# Qwiic_Spectral_Sensor-AS726x.net
KiCad netlist of a schematic drawn in EAGLE
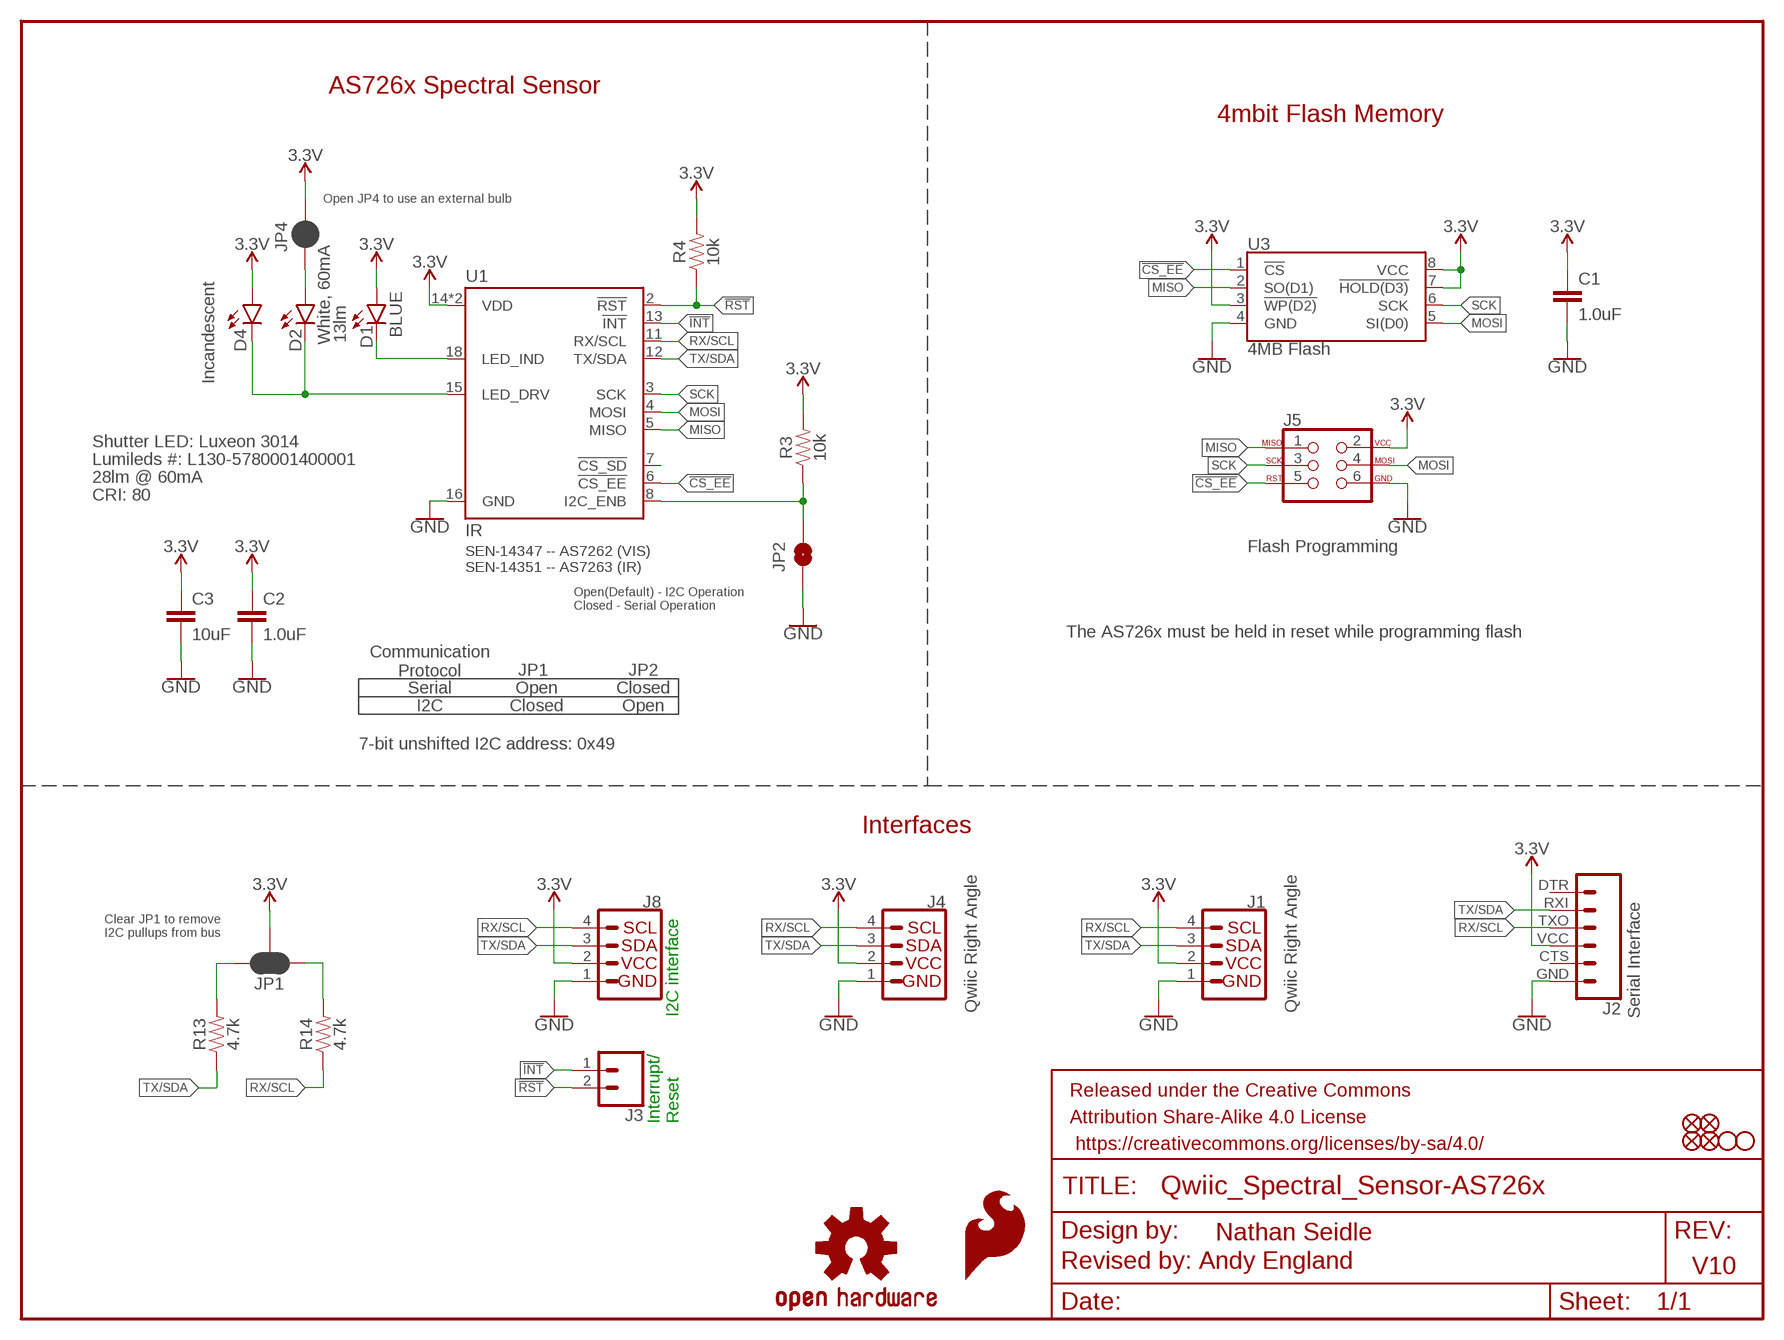
[diagram p0: schematic, sheet 1]

(export (version "E")
  (design (tool "Eeschema 10.0.6"))
  (components
    (comp (ref "C1")
      (value "1.0uF")
      (footprint "eagle-import:0603")
      (libsource (lib "eagle-import") (part "1.0UF-0603-16V-10%"))
    )
    (comp (ref "C2")
      (value "1.0uF")
      (footprint "eagle-import:0603")
      (libsource (lib "eagle-import") (part "1.0UF-0603-16V-10%"))
    )
    (comp (ref "C3")
      (value "10uF")
      (footprint "eagle-import:0603")
      (libsource (lib "eagle-import") (part "10UF-0603-6.3V-20%"))
    )
    (comp (ref "D1")
      (value "BLUE")
      (footprint "eagle-import:LED-0603")
      (libsource (lib "eagle-import") (part "LED-BLUE0603"))
    )
    (comp (ref "D2")
      (value "White, 60mA")
      (footprint "eagle-import:SUPER_BRIGHT_SMD_LED_3014")
      (libsource (lib "eagle-import") (part "LED-WHITE3014"))
    )
    (comp (ref "D4")
      (value "Incandescent")
      (footprint "eagle-import:LED_5MM_NOSILK")
      (libsource (lib "eagle-import") (part "LEDNS"))
    )
    (comp (ref "FD1")
      (value "FIDUCIAL1X2")
      (footprint "eagle-import:FIDUCIAL-1X2")
      (libsource (lib "eagle-import") (part "FIDUCIAL1X2"))
    )
    (comp (ref "FD2")
      (value "FIDUCIAL1X2")
      (footprint "eagle-import:FIDUCIAL-1X2")
      (libsource (lib "eagle-import") (part "FIDUCIAL1X2"))
    )
    (comp (ref "FD3")
      (value "FIDUCIAL1X2")
      (footprint "eagle-import:FIDUCIAL-1X2")
      (libsource (lib "eagle-import") (part "FIDUCIAL1X2"))
    )
    (comp (ref "FD4")
      (value "FIDUCIAL1X2")
      (footprint "eagle-import:FIDUCIAL-1X2")
      (libsource (lib "eagle-import") (part "FIDUCIAL1X2"))
    )
    (comp (ref "FRAME1")
      (value "FRAME-LETTER")
      (footprint "eagle-import:CREATIVE_COMMONS")
      (libsource (lib "eagle-import") (part "FRAME-LETTER"))
    )
    (comp (ref "H2")
      (value "STAND-OFF")
      (footprint "eagle-import:STAND-OFF")
      (libsource (lib "eagle-import") (part "STAND-OFF"))
    )
    (comp (ref "H4")
      (value "STAND-OFF")
      (footprint "eagle-import:STAND-OFF")
      (libsource (lib "eagle-import") (part "STAND-OFF"))
    )
    (comp (ref "J1")
      (value "Qwiic Right Angle")
      (footprint "eagle-import:1X04_1MM_RA")
      (libsource (lib "eagle-import") (part "I2C_STANDARDQWIIC"))
    )
    (comp (ref "J2")
      (value "Serial Interface")
      (footprint "eagle-import:FTDI_BASIC")
      (libsource (lib "eagle-import") (part "6_PIN_SERIAL_CABLEPTH"))
    )
    (comp (ref "J3")
      (value "CONN_021X02_NO_SILK")
      (footprint "eagle-import:1X02_NO_SILK")
      (libsource (lib "eagle-import") (part "CONN_021X02_NO_SILK"))
    )
    (comp (ref "J4")
      (value "Qwiic Right Angle")
      (footprint "eagle-import:1X04_1MM_RA")
      (libsource (lib "eagle-import") (part "I2C_STANDARDQWIIC"))
    )
    (comp (ref "J5")
      (value "Flash Programming")
      (footprint "eagle-import:2X3_TEST_POINTS")
      (libsource (lib "eagle-import") (part "AVR_SPI_PROG_3X2TESTPOINTS"))
    )
    (comp (ref "J8")
      (value "I2C_STANDARD_NO_SILK")
      (footprint "eagle-import:1X04_NO_SILK")
      (libsource (lib "eagle-import") (part "I2C_STANDARD_NO_SILK"))
    )
    (comp (ref "JP1")
      (value "JUMPER-SMT_3_2-NC_PASTE_SILK")
      (footprint "eagle-import:SMT-JUMPER_3_2-NC_PASTE_SILK")
      (libsource (lib "eagle-import") (part "JUMPER-SMT_3_2-NC_PASTE_SILK"))
    )
    (comp (ref "JP2")
      (value "JUMPER-SMT_2_NO_SILK")
      (footprint "eagle-import:SMT-JUMPER_2_NO_SILK")
      (libsource (lib "eagle-import") (part "JUMPER-SMT_2_NO_SILK"))
    )
    (comp (ref "JP4")
      (value "JUMPER-SMT_2_NC_PASTE_NO-SILK")
      (footprint "eagle-import:SMT-JUMPER_2_NC_PASTE_NO-SILK")
      (libsource (lib "eagle-import") (part "JUMPER-SMT_2_NC_PASTE_NO-SILK"))
    )
    (comp (ref "LOGO1")
      (value "SFE_LOGO_FLAME.2_INCH")
      (footprint "eagle-import:SFE_LOGO_FLAME_.2")
      (libsource (lib "eagle-import") (part "SFE_LOGO_FLAME.2_INCH"))
    )
    (comp (ref "LOGO2")
      (value "SFE_LOGO_FLAME.2_INCH")
      (footprint "eagle-import:SFE_LOGO_FLAME_.2")
      (libsource (lib "eagle-import") (part "SFE_LOGO_FLAME.2_INCH"))
    )
    (comp (ref "LOGO4")
      (value "OSHW-LOGOS")
      (footprint "eagle-import:OSHW-LOGO-S")
      (libsource (lib "eagle-import") (part "OSHW-LOGOS"))
    )
    (comp (ref "R3")
      (value "10k")
      (footprint "eagle-import:0603")
      (libsource (lib "eagle-import") (part "10KOHM-0603-1/10W-1%"))
    )
    (comp (ref "R4")
      (value "10k")
      (footprint "eagle-import:0603")
      (libsource (lib "eagle-import") (part "10KOHM-0603-1/10W-1%"))
    )
    (comp (ref "R13")
      (value "4.7k")
      (footprint "eagle-import:0603")
      (libsource (lib "eagle-import") (part "4.7KOHM-0603-1/10W-1%"))
    )
    (comp (ref "R14")
      (value "4.7k")
      (footprint "eagle-import:0603")
      (libsource (lib "eagle-import") (part "4.7KOHM-0603-1/10W-1%"))
    )
    (comp (ref "U1")
      (value "IR")
      (footprint "eagle-import:LGA20")
      (libsource (lib "eagle-import") (part "AS726XIR"))
    )
    (comp (ref "U3")
      (value "4MB Flash")
      (footprint "eagle-import:SO08")
      (libsource (lib "eagle-import") (part "AT25SF041"))
    )
  )
  (nets
    (net (code "1") (name "/~{CS_EE}") (class "Default")
      (node (ref "J5") (pin "5") (pinfunction "5_5") (pintype "passive"))
      (node (ref "U1") (pin "6") (pinfunction "~{CS_EE}_6") (pintype "bidirectional"))
      (node (ref "U3") (pin "1") (pinfunction "~{CS}_1") (pintype "bidirectional"))
    )
    (net (code "2") (name "/~{INT}") (class "Default")
      (node (ref "J3") (pin "1") (pinfunction "1_1") (pintype "passive"))
      (node (ref "U1") (pin "13") (pinfunction "~{INT}_13") (pintype "bidirectional"))
    )
    (net (code "3") (name "/~{RST}") (class "Default")
      (node (ref "J3") (pin "2") (pinfunction "2_2") (pintype "passive"))
      (node (ref "R4") (pin "1") (pinfunction "1_1") (pintype "passive"))
      (node (ref "U1") (pin "2") (pinfunction "~{RST}_2") (pintype "bidirectional"))
    )
    (net (code "4") (name "3.3V") (class "Default")
      (node (ref "C1") (pin "1") (pinfunction "1_1") (pintype "passive"))
      (node (ref "C2") (pin "1") (pinfunction "1_1") (pintype "passive"))
      (node (ref "C3") (pin "1") (pinfunction "1_1") (pintype "passive"))
      (node (ref "D1") (pin "A") (pinfunction "A_A") (pintype "passive"))
      (node (ref "D4") (pin "A") (pinfunction "A_A") (pintype "passive"))
      (node (ref "J1") (pin "2") (pinfunction "2_2") (pintype "power_in"))
      (node (ref "J2") (pin "VCC") (pinfunction "4_VCC") (pintype "passive"))
      (node (ref "J4") (pin "2") (pinfunction "2_2") (pintype "power_in"))
      (node (ref "J5") (pin "2") (pinfunction "2_2") (pintype "passive"))
      (node (ref "J8") (pin "2") (pinfunction "2_2") (pintype "power_in"))
      (node (ref "JP1") (pin "2") (pinfunction "2_2") (pintype "passive"))
      (node (ref "JP4") (pin "2") (pinfunction "2_2") (pintype "passive"))
      (node (ref "R3") (pin "2") (pinfunction "2_2") (pintype "passive"))
      (node (ref "R4") (pin "2") (pinfunction "2_2") (pintype "passive"))
      (node (ref "U1") (pin "14") (pinfunction "VDD_14") (pintype "bidirectional"))
      (node (ref "U1") (pin "17") (pinfunction "VDD_17") (pintype "bidirectional"))
      (node (ref "U3") (pin "3") (pinfunction "~{WP(D2})_3") (pintype "bidirectional"))
      (node (ref "U3") (pin "7") (pinfunction "~{HOLD(D3})_7") (pintype "bidirectional"))
      (node (ref "U3") (pin "8") (pinfunction "VCC_8") (pintype "bidirectional"))
    )
    (net (code "5") (name "GND") (class "Default")
      (node (ref "C1") (pin "2") (pinfunction "2_2") (pintype "passive"))
      (node (ref "C2") (pin "2") (pinfunction "2_2") (pintype "passive"))
      (node (ref "C3") (pin "2") (pinfunction "2_2") (pintype "passive"))
      (node (ref "J1") (pin "1") (pinfunction "1_1") (pintype "power_in"))
      (node (ref "J2") (pin "GND") (pinfunction "6_GND") (pintype "passive"))
      (node (ref "J4") (pin "1") (pinfunction "1_1") (pintype "power_in"))
      (node (ref "J5") (pin "6") (pinfunction "6_6") (pintype "passive"))
      (node (ref "J8") (pin "1") (pinfunction "1_1") (pintype "power_in"))
      (node (ref "JP2") (pin "1") (pinfunction "1_1") (pintype "passive"))
      (node (ref "U1") (pin "16") (pinfunction "GND_16") (pintype "bidirectional"))
      (node (ref "U3") (pin "4") (pinfunction "GND_4") (pintype "bidirectional"))
    )
    (net (code "6") (name "MISO") (class "Default")
      (node (ref "J5") (pin "1") (pinfunction "1_1") (pintype "passive"))
      (node (ref "U1") (pin "5") (pinfunction "MISO_5") (pintype "bidirectional"))
      (node (ref "U3") (pin "2") (pinfunction "SO(D1)_2") (pintype "bidirectional"))
    )
    (net (code "7") (name "MOSI") (class "Default")
      (node (ref "J5") (pin "4") (pinfunction "4_4") (pintype "passive"))
      (node (ref "U1") (pin "4") (pinfunction "MOSI_4") (pintype "bidirectional"))
      (node (ref "U3") (pin "5") (pinfunction "SI(D0)_5") (pintype "bidirectional"))
    )
    (net (code "8") (name "Net-(D2-PadA)") (class "Default")
      (node (ref "D2") (pin "A") (pinfunction "A_A") (pintype "passive"))
      (node (ref "JP4") (pin "1") (pinfunction "1_1") (pintype "passive"))
    )
    (net (code "9") (name "Net-(D4-C)") (class "Default")
      (node (ref "D2") (pin "C") (pinfunction "C_C") (pintype "passive"))
      (node (ref "D4") (pin "K") (pinfunction "C_K") (pintype "passive"))
      (node (ref "U1") (pin "15") (pinfunction "LED_DRV_15") (pintype "bidirectional"))
    )
    (net (code "10") (name "Net-(JP1-Pad1)") (class "Default")
      (node (ref "JP1") (pin "1") (pinfunction "1_1") (pintype "passive"))
      (node (ref "R14") (pin "2") (pinfunction "2_2") (pintype "passive"))
    )
    (net (code "11") (name "Net-(JP1-Pad3)") (class "Default")
      (node (ref "JP1") (pin "3") (pinfunction "3_3") (pintype "passive"))
      (node (ref "R13") (pin "2") (pinfunction "2_2") (pintype "passive"))
    )
    (net (code "12") (name "Net-(U1-I2C_ENB)") (class "Default")
      (node (ref "JP2") (pin "2") (pinfunction "2_2") (pintype "passive"))
      (node (ref "R3") (pin "1") (pinfunction "1_1") (pintype "passive"))
      (node (ref "U1") (pin "8") (pinfunction "I2C_ENB_8") (pintype "bidirectional"))
    )
    (net (code "13") (name "Net-(U1-LED_IND)") (class "Default")
      (node (ref "D1") (pin "C") (pinfunction "C_C") (pintype "passive"))
      (node (ref "U1") (pin "18") (pinfunction "LED_IND_18") (pintype "bidirectional"))
    )
    (net (code "14") (name "RX{slash}SCL") (class "Default")
      (node (ref "J1") (pin "4") (pinfunction "4_4") (pintype "passive"))
      (node (ref "J2") (pin "TXO") (pinfunction "3_TXO") (pintype "passive"))
      (node (ref "J4") (pin "4") (pinfunction "4_4") (pintype "passive"))
      (node (ref "J8") (pin "4") (pinfunction "4_4") (pintype "passive"))
      (node (ref "R14") (pin "1") (pinfunction "1_1") (pintype "passive"))
      (node (ref "U1") (pin "11") (pinfunction "RX/SCL_11") (pintype "bidirectional"))
    )
    (net (code "15") (name "SCK") (class "Default")
      (node (ref "J5") (pin "3") (pinfunction "3_3") (pintype "passive"))
      (node (ref "U1") (pin "3") (pinfunction "SCK_3") (pintype "bidirectional"))
      (node (ref "U3") (pin "6") (pinfunction "SCK_6") (pintype "bidirectional"))
    )
    (net (code "16") (name "TX{slash}SDA") (class "Default")
      (node (ref "J1") (pin "3") (pinfunction "3_3") (pintype "passive"))
      (node (ref "J2") (pin "RXI") (pinfunction "2_RXI") (pintype "passive"))
      (node (ref "J4") (pin "3") (pinfunction "3_3") (pintype "passive"))
      (node (ref "J8") (pin "3") (pinfunction "3_3") (pintype "passive"))
      (node (ref "R13") (pin "1") (pinfunction "1_1") (pintype "passive"))
      (node (ref "U1") (pin "12") (pinfunction "TX/SDA_12") (pintype "bidirectional"))
    )
    (net (code "17") (name "unconnected-(J2-1-PadDTR)") (class "Default")
      (node (ref "J2") (pin "DTR") (pinfunction "1_DTR") (pintype "passive"))
    )
    (net (code "18") (name "unconnected-(J2-5-PadCTS)") (class "Default")
      (node (ref "J2") (pin "CTS") (pinfunction "5_CTS") (pintype "passive"))
    )
    (net (code "19") (name "unconnected-(U1-~{CS_SD}-Pad7)") (class "Default")
      (node (ref "U1") (pin "7") (pinfunction "~{CS_SD}_7") (pintype "bidirectional"))
    )
  )
)
